# SampleCtrl.net
KiCad netlist of a schematic drawn in Altium Designer
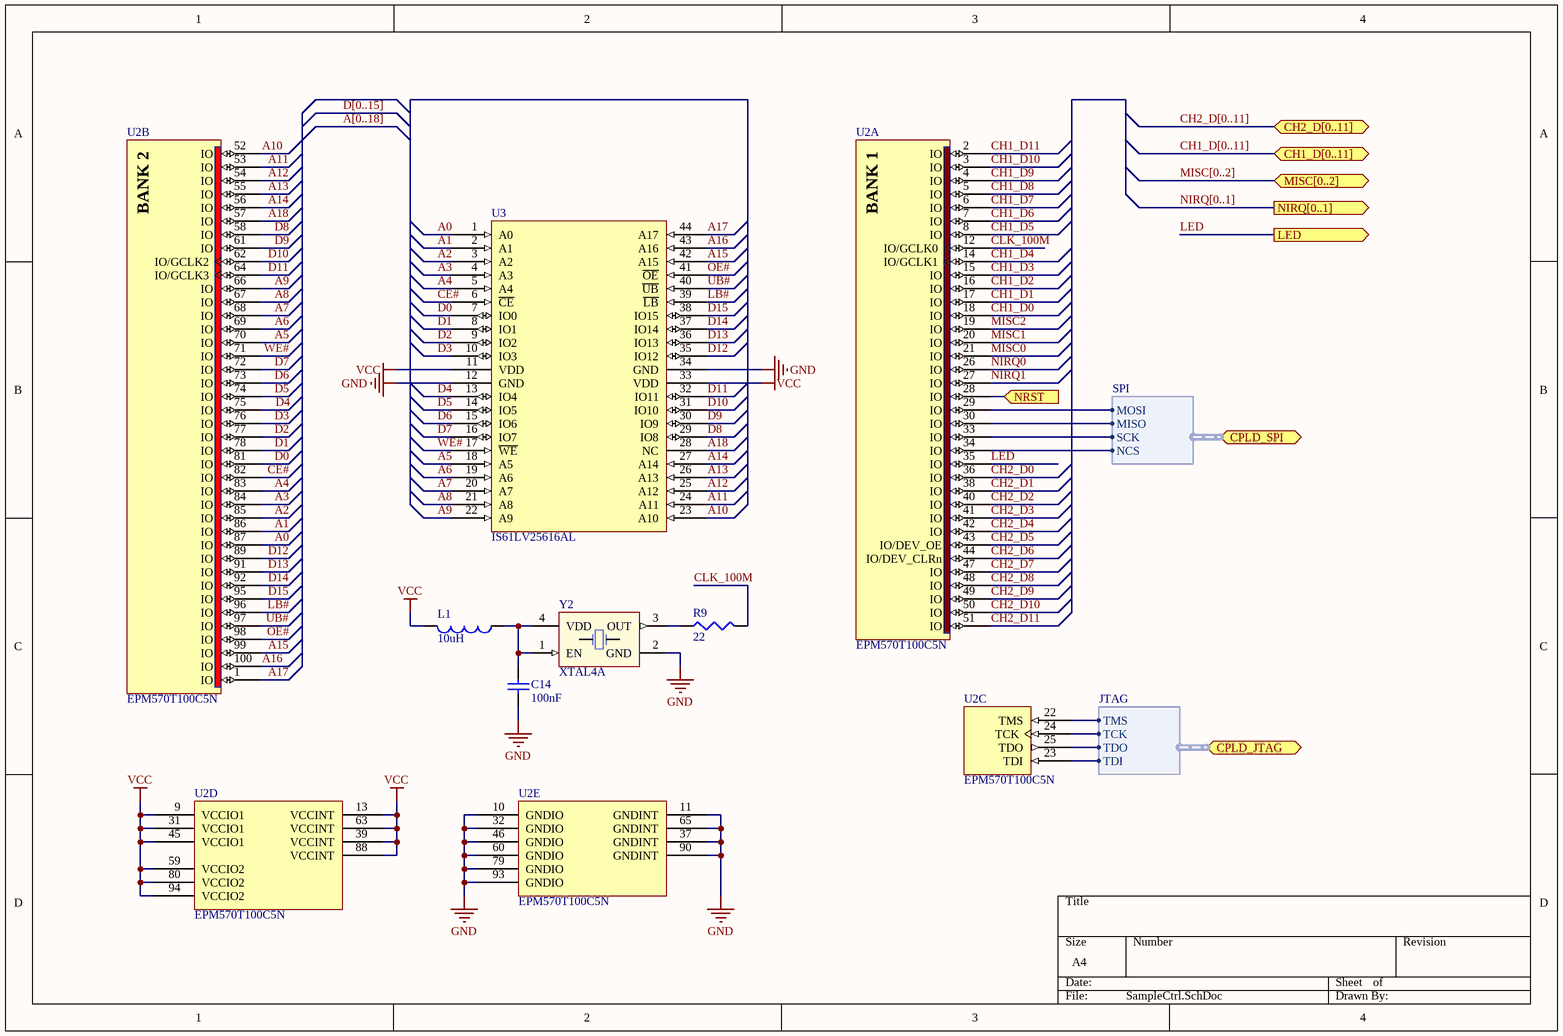
[diagram p0: SampleCtrl.SchDoc]

(export (version "E")
  (design (tool "Eeschema 10.0.6"))
  (components
    (comp (ref "C14")
      (value "100nF")
      (footprint "0603C")
      (description "Capacitor")
      (fields (field (name "Comment") "Cap") (field (name "PUBLISHER") "Altium Limited"))
      (libsource (lib "Miscellaneous Devices") (part "Cap"))
    )
    (comp (ref "L1")
      (value "10uH")
      (footprint "0805L")
      (description "Inductor")
      (fields (field (name "PUBLISHER") "Altium Limited"))
      (libsource (lib "Miscellaneous Devices") (part "Inductor"))
    )
    (comp (ref "R9")
      (value "22")
      (footprint "0603R")
      (description "Resistor")
      (fields (field (name "Comment") "Res3") (field (name "PUBLISHER") "Altium Limited"))
      (libsource (lib "Miscellaneous Devices") (part "Res3"))
    )
    (comp (ref "U2")
      (value "EPM570T100C5N")
      (footprint "TQFP100_N")
      (fields (field (name "PUBLISHER") "Altium Limited"))
      (libsource (lib "Altera MAX II") (part "EPM570T100C5N"))
    )
    (comp (ref "U3")
      (value "IS61LV25616AL")
      (footprint "TSOP-2L")
      (description "256K*16 SRAM, 3.3V")
      (libsource (lib "WiDSO") (part "IS61LV25616AL"))
    )
    (comp (ref "Y2")
      (value "XTAL4A")
      (footprint "XTAL_7050_4P")
      (description "4脚有源晶振")
      (libsource (lib "WiDSO") (part "XTAL4A"))
    )
  )
  (nets
    (net (code "3") (name "/A0") (class "Default")
      (node (ref "U2") (pin "87") (pinfunction "IO_87") (pintype "bidirectional"))
      (node (ref "U3") (pin "1") (pinfunction "A0_1") (pintype "input"))
    )
    (net (code "4") (name "/A1") (class "Default")
      (node (ref "U2") (pin "86") (pinfunction "IO_86") (pintype "bidirectional"))
      (node (ref "U3") (pin "2") (pinfunction "A1_2") (pintype "input"))
    )
    (net (code "5") (name "/A2") (class "Default")
      (node (ref "U2") (pin "85") (pinfunction "IO_85") (pintype "bidirectional"))
      (node (ref "U3") (pin "3") (pinfunction "A2_3") (pintype "input"))
    )
    (net (code "6") (name "/A3") (class "Default")
      (node (ref "U2") (pin "84") (pinfunction "IO_84") (pintype "bidirectional"))
      (node (ref "U3") (pin "4") (pinfunction "A3_4") (pintype "input"))
    )
    (net (code "7") (name "/A4") (class "Default")
      (node (ref "U2") (pin "83") (pinfunction "IO_83") (pintype "bidirectional"))
      (node (ref "U3") (pin "5") (pinfunction "A4_5") (pintype "input"))
    )
    (net (code "8") (name "/A5") (class "Default")
      (node (ref "U2") (pin "70") (pinfunction "IO_70") (pintype "bidirectional"))
      (node (ref "U3") (pin "18") (pinfunction "A5_18") (pintype "input"))
    )
    (net (code "9") (name "/A6") (class "Default")
      (node (ref "U2") (pin "69") (pinfunction "IO_69") (pintype "bidirectional"))
      (node (ref "U3") (pin "19") (pinfunction "A6_19") (pintype "input"))
    )
    (net (code "10") (name "/A7") (class "Default")
      (node (ref "U2") (pin "68") (pinfunction "IO_68") (pintype "bidirectional"))
      (node (ref "U3") (pin "20") (pinfunction "A7_20") (pintype "input"))
    )
    (net (code "11") (name "/A8") (class "Default")
      (node (ref "U2") (pin "67") (pinfunction "IO_67") (pintype "bidirectional"))
      (node (ref "U3") (pin "21") (pinfunction "A8_21") (pintype "input"))
    )
    (net (code "12") (name "/A9") (class "Default")
      (node (ref "U2") (pin "66") (pinfunction "IO_66") (pintype "bidirectional"))
      (node (ref "U3") (pin "22") (pinfunction "A9_22") (pintype "input"))
    )
    (net (code "13") (name "/A10") (class "Default")
      (node (ref "U2") (pin "52") (pinfunction "IO_52") (pintype "bidirectional"))
      (node (ref "U3") (pin "23") (pinfunction "A10_23") (pintype "input"))
    )
    (net (code "14") (name "/A11") (class "Default")
      (node (ref "U2") (pin "53") (pinfunction "IO_53") (pintype "bidirectional"))
      (node (ref "U3") (pin "24") (pinfunction "A11_24") (pintype "input"))
    )
    (net (code "15") (name "/A12") (class "Default")
      (node (ref "U2") (pin "54") (pinfunction "IO_54") (pintype "bidirectional"))
      (node (ref "U3") (pin "25") (pinfunction "A12_25") (pintype "input"))
    )
    (net (code "16") (name "/A13") (class "Default")
      (node (ref "U2") (pin "55") (pinfunction "IO_55") (pintype "bidirectional"))
      (node (ref "U3") (pin "26") (pinfunction "A13_26") (pintype "input"))
    )
    (net (code "17") (name "/A14") (class "Default")
      (node (ref "U2") (pin "56") (pinfunction "IO_56") (pintype "bidirectional"))
      (node (ref "U3") (pin "27") (pinfunction "A14_27") (pintype "input"))
    )
    (net (code "18") (name "/A15") (class "Default")
      (node (ref "U2") (pin "99") (pinfunction "IO_99") (pintype "bidirectional"))
      (node (ref "U3") (pin "42") (pinfunction "A15_42") (pintype "input"))
    )
    (net (code "19") (name "/A16") (class "Default")
      (node (ref "U2") (pin "100") (pinfunction "IO_100") (pintype "bidirectional"))
      (node (ref "U3") (pin "43") (pinfunction "A16_43") (pintype "input"))
    )
    (net (code "20") (name "/A17") (class "Default")
      (node (ref "U2") (pin "1") (pinfunction "IO_1") (pintype "bidirectional"))
      (node (ref "U3") (pin "44") (pinfunction "A17_44") (pintype "input"))
    )
    (net (code "21") (name "/A18") (class "Default")
      (node (ref "U2") (pin "57") (pinfunction "IO_57") (pintype "bidirectional"))
      (node (ref "U3") (pin "28") (pinfunction "NC_28") (pintype "passive"))
    )
    (net (code "23") (name "/CE#") (class "Default")
      (node (ref "U2") (pin "82") (pinfunction "IO_82") (pintype "bidirectional"))
      (node (ref "U3") (pin "6") (pinfunction "~{CE}_6") (pintype "input"))
    )
    (net (code "24") (name "/CH1_D0") (class "Default")
      (node (ref "U2") (pin "18") (pinfunction "IO_18") (pintype "bidirectional"))
    )
    (net (code "25") (name "/CH1_D1") (class "Default")
      (node (ref "U2") (pin "17") (pinfunction "IO_17") (pintype "bidirectional"))
    )
    (net (code "26") (name "/CH1_D2") (class "Default")
      (node (ref "U2") (pin "16") (pinfunction "IO_16") (pintype "bidirectional"))
    )
    (net (code "27") (name "/CH1_D3") (class "Default")
      (node (ref "U2") (pin "15") (pinfunction "IO_15") (pintype "bidirectional"))
    )
    (net (code "28") (name "/CH1_D4") (class "Default")
      (node (ref "U2") (pin "14") (pinfunction "IO/GCLK1_14") (pintype "bidirectional"))
    )
    (net (code "29") (name "/CH1_D5") (class "Default")
      (node (ref "U2") (pin "8") (pinfunction "IO_8") (pintype "bidirectional"))
    )
    (net (code "30") (name "/CH1_D6") (class "Default")
      (node (ref "U2") (pin "7") (pinfunction "IO_7") (pintype "bidirectional"))
    )
    (net (code "31") (name "/CH1_D7") (class "Default")
      (node (ref "U2") (pin "6") (pinfunction "IO_6") (pintype "bidirectional"))
    )
    (net (code "32") (name "/CH1_D8") (class "Default")
      (node (ref "U2") (pin "5") (pinfunction "IO_5") (pintype "bidirectional"))
    )
    (net (code "33") (name "/CH1_D9") (class "Default")
      (node (ref "U2") (pin "4") (pinfunction "IO_4") (pintype "bidirectional"))
    )
    (net (code "34") (name "/CH1_D10") (class "Default")
      (node (ref "U2") (pin "3") (pinfunction "IO_3") (pintype "bidirectional"))
    )
    (net (code "35") (name "/CH1_D11") (class "Default")
      (node (ref "U2") (pin "2") (pinfunction "IO_2") (pintype "bidirectional"))
    )
    (net (code "37") (name "/CH2_D0") (class "Default")
      (node (ref "U2") (pin "36") (pinfunction "IO_36") (pintype "bidirectional"))
    )
    (net (code "38") (name "/CH2_D1") (class "Default")
      (node (ref "U2") (pin "38") (pinfunction "IO_38") (pintype "bidirectional"))
    )
    (net (code "39") (name "/CH2_D2") (class "Default")
      (node (ref "U2") (pin "40") (pinfunction "IO_40") (pintype "bidirectional"))
    )
    (net (code "40") (name "/CH2_D3") (class "Default")
      (node (ref "U2") (pin "41") (pinfunction "IO_41") (pintype "bidirectional"))
    )
    (net (code "41") (name "/CH2_D4") (class "Default")
      (node (ref "U2") (pin "42") (pinfunction "IO_42") (pintype "bidirectional"))
    )
    (net (code "42") (name "/CH2_D5") (class "Default")
      (node (ref "U2") (pin "43") (pinfunction "IO/DEV_OE_43") (pintype "bidirectional"))
    )
    (net (code "43") (name "/CH2_D6") (class "Default")
      (node (ref "U2") (pin "44") (pinfunction "IO/DEV_CLRn_44") (pintype "bidirectional"))
    )
    (net (code "44") (name "/CH2_D7") (class "Default")
      (node (ref "U2") (pin "47") (pinfunction "IO_47") (pintype "bidirectional"))
    )
    (net (code "45") (name "/CH2_D8") (class "Default")
      (node (ref "U2") (pin "48") (pinfunction "IO_48") (pintype "bidirectional"))
    )
    (net (code "46") (name "/CH2_D9") (class "Default")
      (node (ref "U2") (pin "49") (pinfunction "IO_49") (pintype "bidirectional"))
    )
    (net (code "47") (name "/CH2_D10") (class "Default")
      (node (ref "U2") (pin "50") (pinfunction "IO_50") (pintype "bidirectional"))
    )
    (net (code "48") (name "/CH2_D11") (class "Default")
      (node (ref "U2") (pin "51") (pinfunction "IO_51") (pintype "bidirectional"))
    )
    (net (code "50") (name "/CLK_100M") (class "Default")
      (node (ref "R9") (pin "2") (pinfunction "2_2") (pintype "passive"))
      (node (ref "U2") (pin "12") (pinfunction "IO/GCLK0_12") (pintype "bidirectional"))
    )
    (net (code "51") (name "/D0") (class "Default")
      (node (ref "U2") (pin "81") (pinfunction "IO_81") (pintype "bidirectional"))
      (node (ref "U3") (pin "7") (pinfunction "IO0_7") (pintype "bidirectional"))
    )
    (net (code "52") (name "/D1") (class "Default")
      (node (ref "U2") (pin "78") (pinfunction "IO_78") (pintype "bidirectional"))
      (node (ref "U3") (pin "8") (pinfunction "IO1_8") (pintype "bidirectional"))
    )
    (net (code "53") (name "/D2") (class "Default")
      (node (ref "U2") (pin "77") (pinfunction "IO_77") (pintype "bidirectional"))
      (node (ref "U3") (pin "9") (pinfunction "IO2_9") (pintype "bidirectional"))
    )
    (net (code "54") (name "/D3") (class "Default")
      (node (ref "U2") (pin "76") (pinfunction "IO_76") (pintype "bidirectional"))
      (node (ref "U3") (pin "10") (pinfunction "IO3_10") (pintype "bidirectional"))
    )
    (net (code "55") (name "/D4") (class "Default")
      (node (ref "U2") (pin "75") (pinfunction "IO_75") (pintype "bidirectional"))
      (node (ref "U3") (pin "13") (pinfunction "IO4_13") (pintype "bidirectional"))
    )
    (net (code "56") (name "/D5") (class "Default")
      (node (ref "U2") (pin "74") (pinfunction "IO_74") (pintype "bidirectional"))
      (node (ref "U3") (pin "14") (pinfunction "IO5_14") (pintype "bidirectional"))
    )
    (net (code "57") (name "/D6") (class "Default")
      (node (ref "U2") (pin "73") (pinfunction "IO_73") (pintype "bidirectional"))
      (node (ref "U3") (pin "15") (pinfunction "IO6_15") (pintype "bidirectional"))
    )
    (net (code "58") (name "/D7") (class "Default")
      (node (ref "U2") (pin "72") (pinfunction "IO_72") (pintype "bidirectional"))
      (node (ref "U3") (pin "16") (pinfunction "IO7_16") (pintype "bidirectional"))
    )
    (net (code "59") (name "/D8") (class "Default")
      (node (ref "U2") (pin "58") (pinfunction "IO_58") (pintype "bidirectional"))
      (node (ref "U3") (pin "29") (pinfunction "IO8_29") (pintype "bidirectional"))
    )
    (net (code "60") (name "/D9") (class "Default")
      (node (ref "U2") (pin "61") (pinfunction "IO_61") (pintype "bidirectional"))
      (node (ref "U3") (pin "30") (pinfunction "IO9_30") (pintype "bidirectional"))
    )
    (net (code "61") (name "/D10") (class "Default")
      (node (ref "U2") (pin "62") (pinfunction "IO/GCLK2_62") (pintype "bidirectional"))
      (node (ref "U3") (pin "31") (pinfunction "IO10_31") (pintype "bidirectional"))
    )
    (net (code "62") (name "/D11") (class "Default")
      (node (ref "U2") (pin "64") (pinfunction "IO/GCLK3_64") (pintype "bidirectional"))
      (node (ref "U3") (pin "32") (pinfunction "IO11_32") (pintype "bidirectional"))
    )
    (net (code "63") (name "/D12") (class "Default")
      (node (ref "U2") (pin "89") (pinfunction "IO_89") (pintype "bidirectional"))
      (node (ref "U3") (pin "35") (pinfunction "IO12_35") (pintype "bidirectional"))
    )
    (net (code "64") (name "/D13") (class "Default")
      (node (ref "U2") (pin "91") (pinfunction "IO_91") (pintype "bidirectional"))
      (node (ref "U3") (pin "36") (pinfunction "IO13_36") (pintype "bidirectional"))
    )
    (net (code "65") (name "/D14") (class "Default")
      (node (ref "U2") (pin "92") (pinfunction "IO_92") (pintype "bidirectional"))
      (node (ref "U3") (pin "37") (pinfunction "IO14_37") (pintype "bidirectional"))
    )
    (net (code "66") (name "/D15") (class "Default")
      (node (ref "U2") (pin "95") (pinfunction "IO_95") (pintype "bidirectional"))
      (node (ref "U3") (pin "38") (pinfunction "IO15_38") (pintype "bidirectional"))
    )
    (net (code "68") (name "/LB#") (class "Default")
      (node (ref "U2") (pin "96") (pinfunction "IO_96") (pintype "bidirectional"))
      (node (ref "U3") (pin "39") (pinfunction "~{LB}_39") (pintype "input"))
    )
    (net (code "69") (name "/LED") (class "Default")
      (node (ref "U2") (pin "35") (pinfunction "IO_35") (pintype "bidirectional"))
    )
    (net (code "70") (name "/MISC0") (class "Default")
      (node (ref "U2") (pin "21") (pinfunction "IO_21") (pintype "bidirectional"))
    )
    (net (code "71") (name "/MISC1") (class "Default")
      (node (ref "U2") (pin "20") (pinfunction "IO_20") (pintype "bidirectional"))
    )
    (net (code "72") (name "/MISC2") (class "Default")
      (node (ref "U2") (pin "19") (pinfunction "IO_19") (pintype "bidirectional"))
    )
    (net (code "74") (name "/MISO") (class "Default")
      (node (ref "U2") (pin "30") (pinfunction "IO_30") (pintype "bidirectional"))
    )
    (net (code "75") (name "/MOSI") (class "Default")
      (node (ref "U2") (pin "29") (pinfunction "IO_29") (pintype "bidirectional"))
    )
    (net (code "76") (name "/NCS") (class "Default")
      (node (ref "U2") (pin "34") (pinfunction "IO_34") (pintype "bidirectional"))
    )
    (net (code "77") (name "/NIRQ0") (class "Default")
      (node (ref "U2") (pin "26") (pinfunction "IO_26") (pintype "bidirectional"))
    )
    (net (code "78") (name "/NIRQ1") (class "Default")
      (node (ref "U2") (pin "27") (pinfunction "IO_27") (pintype "bidirectional"))
    )
    (net (code "80") (name "/NRST") (class "Default")
      (node (ref "U2") (pin "28") (pinfunction "IO_28") (pintype "bidirectional"))
    )
    (net (code "81") (name "/OE#") (class "Default")
      (node (ref "U2") (pin "98") (pinfunction "IO_98") (pintype "bidirectional"))
      (node (ref "U3") (pin "41") (pinfunction "~{OE}_41") (pintype "input"))
    )
    (net (code "82") (name "/SCK") (class "Default")
      (node (ref "U2") (pin "33") (pinfunction "IO_33") (pintype "bidirectional"))
    )
    (net (code "83") (name "/TCK") (class "Default")
      (node (ref "U2") (pin "24") (pinfunction "TCK_24") (pintype "input"))
    )
    (net (code "84") (name "/TDI") (class "Default")
      (node (ref "U2") (pin "23") (pinfunction "TDI_23") (pintype "input"))
    )
    (net (code "85") (name "/TDO") (class "Default")
      (node (ref "U2") (pin "25") (pinfunction "TDO_25") (pintype "output"))
    )
    (net (code "86") (name "/TMS") (class "Default")
      (node (ref "U2") (pin "22") (pinfunction "TMS_22") (pintype "input"))
    )
    (net (code "87") (name "/UB#") (class "Default")
      (node (ref "U2") (pin "97") (pinfunction "IO_97") (pintype "bidirectional"))
      (node (ref "U3") (pin "40") (pinfunction "~{UB}_40") (pintype "input"))
    )
    (net (code "88") (name "/WE#") (class "Default")
      (node (ref "U2") (pin "71") (pinfunction "IO_71") (pintype "bidirectional"))
      (node (ref "U3") (pin "17") (pinfunction "~{WE}_17") (pintype "input"))
    )
    (net (code "91") (name "GND") (class "Default")
      (node (ref "C14") (pin "2") (pinfunction "2_2") (pintype "passive"))
      (node (ref "U2") (pin "10") (pinfunction "GNDIO_10") (pintype "power_in"))
      (node (ref "U2") (pin "11") (pinfunction "GNDINT_11") (pintype "power_in"))
      (node (ref "U2") (pin "32") (pinfunction "GNDIO_32") (pintype "power_in"))
      (node (ref "U2") (pin "37") (pinfunction "GNDINT_37") (pintype "power_in"))
      (node (ref "U2") (pin "46") (pinfunction "GNDIO_46") (pintype "power_in"))
      (node (ref "U2") (pin "60") (pinfunction "GNDIO_60") (pintype "power_in"))
      (node (ref "U2") (pin "65") (pinfunction "GNDINT_65") (pintype "power_in"))
      (node (ref "U2") (pin "79") (pinfunction "GNDIO_79") (pintype "power_in"))
      (node (ref "U2") (pin "90") (pinfunction "GNDINT_90") (pintype "power_in"))
      (node (ref "U2") (pin "93") (pinfunction "GNDIO_93") (pintype "power_in"))
      (node (ref "U3") (pin "12") (pinfunction "GND_12") (pintype "power_in"))
      (node (ref "U3") (pin "34") (pinfunction "GND_34") (pintype "power_in"))
      (node (ref "Y2") (pin "2") (pinfunction "GND_2") (pintype "power_in"))
    )
    (net (code "92") (name "Net-(Y2-EN)") (class "Default")
      (node (ref "C14") (pin "1") (pinfunction "1_1") (pintype "passive"))
      (node (ref "L1") (pin "1") (pinfunction "1_1") (pintype "passive"))
      (node (ref "Y2") (pin "1") (pinfunction "EN_1") (pintype "input"))
      (node (ref "Y2") (pin "4") (pinfunction "VDD_4") (pintype "power_in"))
    )
    (net (code "93") (name "Net-(Y2-OUT)") (class "Default")
      (node (ref "R9") (pin "1") (pinfunction "1_1") (pintype "passive"))
      (node (ref "Y2") (pin "3") (pinfunction "OUT_3") (pintype "output"))
    )
    (net (code "94") (name "VCC") (class "Default")
      (node (ref "L1") (pin "2") (pinfunction "2_2") (pintype "passive"))
      (node (ref "U2") (pin "13") (pinfunction "VCCINT_13") (pintype "power_in"))
      (node (ref "U2") (pin "31") (pinfunction "VCCIO1_31") (pintype "power_in"))
      (node (ref "U2") (pin "39") (pinfunction "VCCINT_39") (pintype "power_in"))
      (node (ref "U2") (pin "45") (pinfunction "VCCIO1_45") (pintype "power_in"))
      (node (ref "U2") (pin "59") (pinfunction "VCCIO2_59") (pintype "power_in"))
      (node (ref "U2") (pin "63") (pinfunction "VCCINT_63") (pintype "power_in"))
      (node (ref "U2") (pin "80") (pinfunction "VCCIO2_80") (pintype "power_in"))
      (node (ref "U2") (pin "88") (pinfunction "VCCINT_88") (pintype "power_in"))
      (node (ref "U2") (pin "9") (pinfunction "VCCIO1_9") (pintype "power_in"))
      (node (ref "U2") (pin "94") (pinfunction "VCCIO2_94") (pintype "power_in"))
      (node (ref "U3") (pin "11") (pinfunction "VDD_11") (pintype "power_in"))
      (node (ref "U3") (pin "33") (pinfunction "VDD_33") (pintype "power_in"))
    )
  )
)
